# MCU.net
KiCad netlist of a schematic drawn in Altium Designer
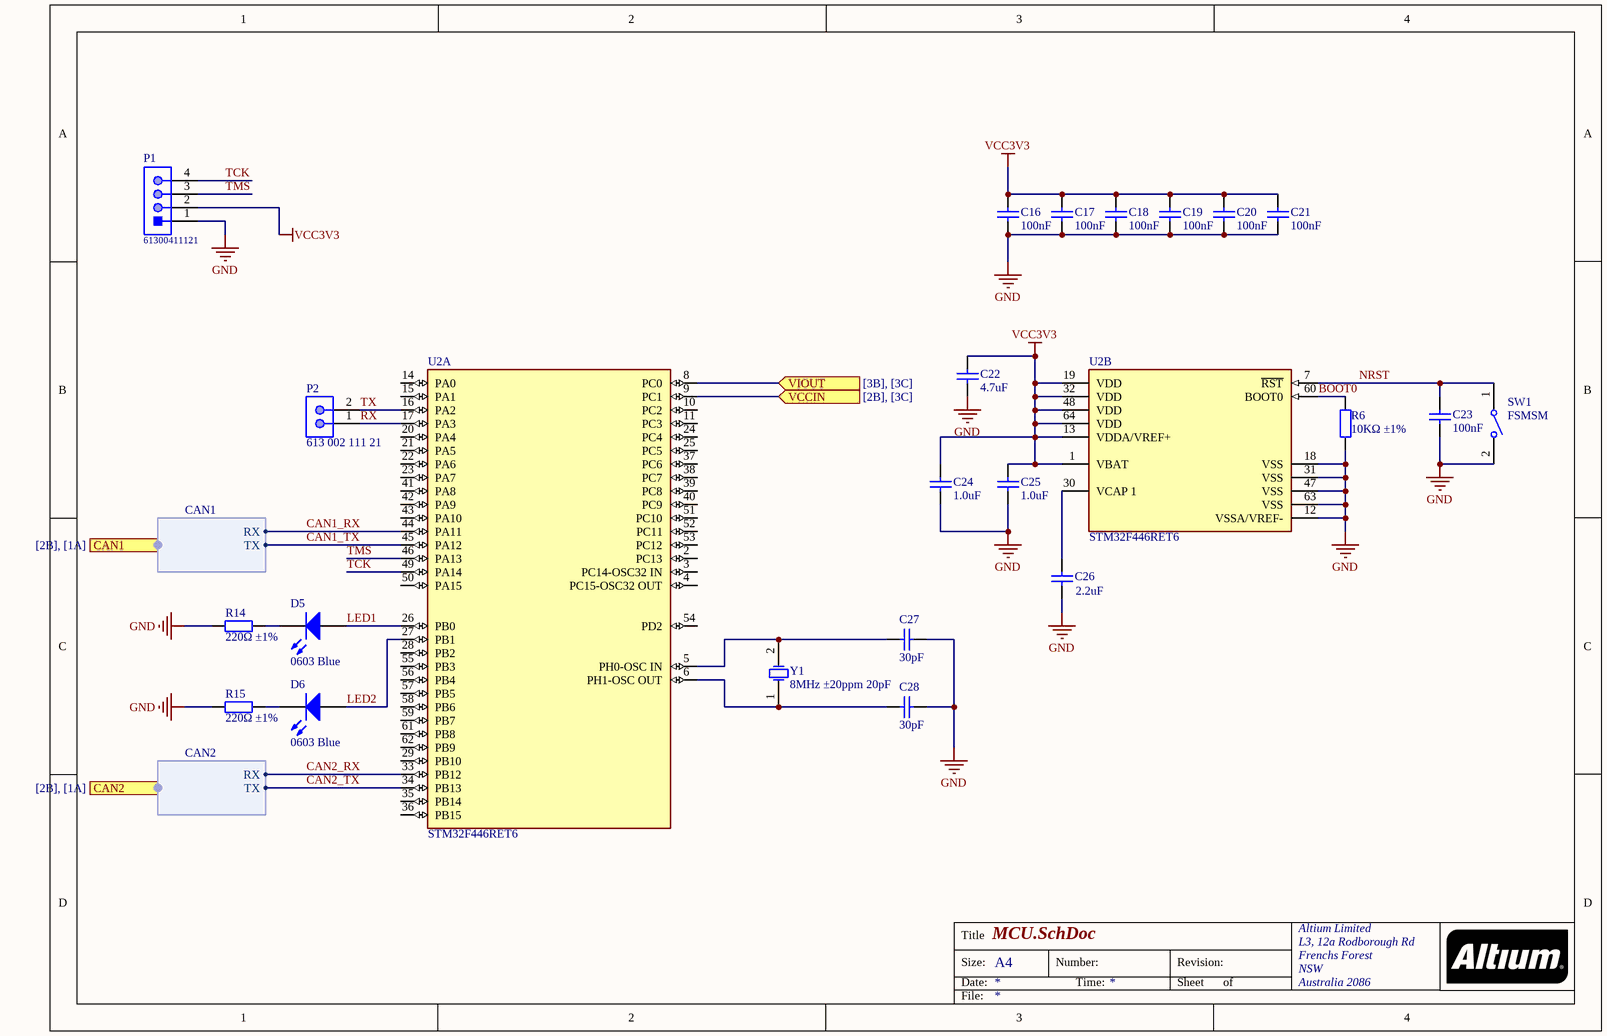
[diagram p0: MCU.SchDoc]

(export (version "E")
  (design (tool "Eeschema 10.0.6"))
  (components
    (comp (ref "C16")
      (value "100nF")
      (footprint "0402_C")
      (description "Chip capacitors")
      (fields
        (field (name "MANUFACTURER") "Samsung Electro-Mechanics")
        (field (name "PARTNUMBER") "CL05B104KO5NNNC")
      )
      (libsource (lib "Miscellaneous Devices LC") (part "0402 100nF (104) 10% 16V"))
    )
    (comp (ref "C17")
      (value "100nF")
      (footprint "0402_C")
      (description "Chip capacitors")
      (fields
        (field (name "MANUFACTURER") "Samsung Electro-Mechanics")
        (field (name "PARTNUMBER") "CL05B104KO5NNNC")
      )
      (libsource (lib "Miscellaneous Devices LC") (part "0402 100nF (104) 10% 16V"))
    )
    (comp (ref "C18")
      (value "100nF")
      (footprint "0402_C")
      (description "Chip capacitors")
      (fields
        (field (name "MANUFACTURER") "Samsung Electro-Mechanics")
        (field (name "PARTNUMBER") "CL05B104KO5NNNC")
      )
      (libsource (lib "Miscellaneous Devices LC") (part "0402 100nF (104) 10% 16V"))
    )
    (comp (ref "C19")
      (value "100nF")
      (footprint "0402_C")
      (description "Chip capacitors")
      (fields
        (field (name "MANUFACTURER") "Samsung Electro-Mechanics")
        (field (name "PARTNUMBER") "CL05B104KO5NNNC")
      )
      (libsource (lib "Miscellaneous Devices LC") (part "0402 100nF (104) 10% 16V"))
    )
    (comp (ref "C20")
      (value "100nF")
      (footprint "0402_C")
      (description "Chip capacitors")
      (fields
        (field (name "MANUFACTURER") "Samsung Electro-Mechanics")
        (field (name "PARTNUMBER") "CL05B104KO5NNNC")
      )
      (libsource (lib "Miscellaneous Devices LC") (part "0402 100nF (104) 10% 16V"))
    )
    (comp (ref "C21")
      (value "100nF")
      (footprint "0402_C")
      (description "Chip capacitors")
      (fields
        (field (name "MANUFACTURER") "Samsung Electro-Mechanics")
        (field (name "PARTNUMBER") "CL05B104KO5NNNC")
      )
      (libsource (lib "Miscellaneous Devices LC") (part "0402 100nF (104) 10% 16V"))
    )
    (comp (ref "C22")
      (value "4.7uF")
      (footprint "0402_C")
      (description "Chip capacitor")
      (fields
        (field (name "MANUFACTURER") "Samsung Electro-Mechanics")
        (field (name "PARTNUMBER") "CL05A475MP5NRNC")
      )
      (libsource (lib "Miscellaneous Devices LC") (part "0402 4.7uF (475) 20% 10V"))
    )
    (comp (ref "C23")
      (value "100nF")
      (footprint "0402_C")
      (description "Chip capacitors")
      (fields
        (field (name "MANUFACTURER") "Samsung Electro-Mechanics")
        (field (name "PARTNUMBER") "CL05B104KO5NNNC")
      )
      (libsource (lib "Miscellaneous Devices LC") (part "0402 100nF (104) 10% 16V"))
    )
    (comp (ref "C24")
      (value "1.0uF")
      (footprint "0402_C")
      (description "Chip capacitor")
      (fields
        (field (name "MANUFACTURER") "Samsung Electro-Mechanics")
        (field (name "PARTNUMBER") "CL05A105KA5NQNC")
      )
      (libsource (lib "Miscellaneous Devices LC") (part "0402 1.0uF (105) 10% 25V"))
    )
    (comp (ref "C25")
      (value "1.0uF")
      (footprint "0402_C")
      (description "Chip capacitor")
      (fields
        (field (name "MANUFACTURER") "Samsung Electro-Mechanics")
        (field (name "PARTNUMBER") "CL05A105KA5NQNC")
      )
      (libsource (lib "Miscellaneous Devices LC") (part "0402 1.0uF (105) 10% 25V"))
    )
    (comp (ref "C26")
      (value "2.2uF")
      (footprint "0603_C")
      (description "Chip capacitors")
      (fields
        (field (name "MANUFACTURER") "Samsung Electro-Mechanics")
        (field (name "PARTNUMBER") "CL10A225KO8NNNC")
      )
      (libsource (lib "Miscellaneous Devices LC") (part "0603 2.2uF (225) 10% 16V"))
    )
    (comp (ref "C27")
      (value "30pF")
      (footprint "0402_C")
      (description "Chip capacitors")
      (fields
        (field (name "MANUFACTURER") "Guangdong Fenghua Advanced Tech")
        (field (name "PARTNUMBER") "0402CG300J500NT")
      )
      (libsource (lib "Miscellaneous Devices LC") (part "0402 30pF (300) 5% 50V"))
    )
    (comp (ref "C28")
      (value "30pF")
      (footprint "0402_C")
      (description "Chip capacitors")
      (fields
        (field (name "MANUFACTURER") "Guangdong Fenghua Advanced Tech")
        (field (name "PARTNUMBER") "0402CG300J500NT")
      )
      (libsource (lib "Miscellaneous Devices LC") (part "0402 30pF (300) 5% 50V"))
    )
    (comp (ref "D5")
      (value "0603 Blue")
      (footprint "0603_LED_S1")
      (description "LED")
      (libsource (lib "Miscellaneous Devices LC") (part "0603 LED Blue"))
    )
    (comp (ref "D6")
      (value "0603 Blue")
      (footprint "0603_LED_S1")
      (description "LED")
      (libsource (lib "Miscellaneous Devices LC") (part "0603 LED Blue"))
    )
    (comp (ref "P1")
      (value "61300411121")
      (footprint "61300411121")
      (description "THT Vertical Pin Header WR-PHD, Pitch 2.54 mm, Single Row, 4 pins")
      (fields (field (name "MANUFACTURER") "Wurth Elektronik") (field (name "PUBLISHER") "WurthElektronik"))
      (libsource (lib "Altium Content Vault") (part "WE-CN-1P-M-R4"))
    )
    (comp (ref "P2")
      (value "613 002 111 21")
      (footprint "WE-61300211121_V")
      (libsource (lib "Altium Content Vault") (part "CN-1P-M-R2"))
    )
    (comp (ref "R6")
      (value "10KΩ ±1%")
      (footprint "0805_R")
      (description "Chip resistor")
      (fields (field (name "MANUFACTURER") "Uniroyal Elec") (field (name "POWER") "1/8W"))
      (libsource (lib "Miscellaneous Devices LC") (part "0805 10K (1002) 1%"))
    )
    (comp (ref "R14")
      (value "220Ω ±1%")
      (footprint "0402_R")
      (description "Chip resistor")
      (fields (field (name "MANUFACTURER") "Uniroyal Elec") (field (name "PARTNUMBER") "0402WGF2200TCE"))
      (libsource (lib "Miscellaneous Devices LC") (part "0402 220R (2200) 1%"))
    )
    (comp (ref "R15")
      (value "220Ω ±1%")
      (footprint "0402_R")
      (description "Chip resistor")
      (fields (field (name "MANUFACTURER") "Uniroyal Elec") (field (name "PARTNUMBER") "0402WGF2200TCE"))
      (libsource (lib "Miscellaneous Devices LC") (part "0402 220R (2200) 1%"))
    )
    (comp (ref "SW1")
      (value "FSMSM")
      (footprint "TECO-FSMSM-2_V")
      (description "FSMSM Push Button Switch, 50 mA, -35 to 85 degC, 2-Pin SMD, RoHS, Bulk")
      (fields (field (name "MANUFACTURER") "TE Connectivity"))
      (libsource (lib "Altium Content Vault") (part "SW-SPST-2_C"))
    )
    (comp (ref "U2")
      (value "STM32F446RET6")
      (footprint "FP-LQFP64-5W-MFG")
      (description "IC MCU 32BIT 512KB FLASH 64LQFP")
      (fields
        (field (name "OCTOPART") "https://octopart.com/stm32f446ret6-stmicroelectronics-52642920")
        (field (name "MANUFACTURER") "ST")
      )
      (libsource (lib "Altium Content Vault") (part "ee11adc32c0ab33b933cccf4348c338"))
    )
    (comp (ref "Y1")
      (value "8MHz ±20ppm 20pF")
      (footprint "SMD-5032_2P")
      (description "贴片晶振")
      (libsource (lib "Miscellaneous Devices LC") (part "SMD-5032_2P 8MHz 20ppm 20pF"))
    )
  )
  (nets
    (net (code "3") (name "/BOOT0") (class "Default")
      (node (ref "R6") (pin "2") (pinfunction "2_2") (pintype "passive"))
      (node (ref "U2") (pin "60") (pinfunction "BOOT0_60") (pintype "input"))
    )
    (net (code "4") (name "/CAN1_RX") (class "Default")
      (node (ref "U2") (pin "44") (pinfunction "PA11_44") (pintype "bidirectional"))
    )
    (net (code "5") (name "/CAN1_TX") (class "Default")
      (node (ref "U2") (pin "45") (pinfunction "PA12_45") (pintype "bidirectional"))
    )
    (net (code "6") (name "/CAN2_RX") (class "Default")
      (node (ref "U2") (pin "33") (pinfunction "PB12_33") (pintype "bidirectional"))
    )
    (net (code "7") (name "/CAN2_TX") (class "Default")
      (node (ref "U2") (pin "34") (pinfunction "PB13_34") (pintype "bidirectional"))
    )
    (net (code "8") (name "/LED1") (class "Default")
      (node (ref "D5") (pin "A") (pinfunction "A_A") (pintype "passive"))
      (node (ref "U2") (pin "26") (pinfunction "PB0_26") (pintype "bidirectional"))
    )
    (net (code "9") (name "/LED2") (class "Default")
      (node (ref "D6") (pin "A") (pinfunction "A_A") (pintype "passive"))
      (node (ref "U2") (pin "27") (pinfunction "PB1_27") (pintype "bidirectional"))
    )
    (net (code "10") (name "/NRST") (class "Default")
      (node (ref "C23") (pin "2") (pinfunction "2_2") (pintype "passive"))
      (node (ref "SW1") (pin "1") (pinfunction "1_1") (pintype "passive"))
      (node (ref "U2") (pin "7") (pinfunction "~{RST}_7") (pintype "input"))
    )
    (net (code "11") (name "/RX") (class "Default")
      (node (ref "P2") (pin "1") (pinfunction "1_1") (pintype "passive"))
      (node (ref "U2") (pin "17") (pinfunction "PA3_17") (pintype "bidirectional"))
    )
    (net (code "12") (name "/TCK") (class "Default")
      (node (ref "P1") (pin "4") (pinfunction "4_4") (pintype "passive"))
      (node (ref "U2") (pin "49") (pinfunction "PA14_49") (pintype "bidirectional"))
    )
    (net (code "13") (name "/TMS") (class "Default")
      (node (ref "P1") (pin "3") (pinfunction "3_3") (pintype "passive"))
      (node (ref "U2") (pin "46") (pinfunction "PA13_46") (pintype "bidirectional"))
    )
    (net (code "14") (name "/TX") (class "Default")
      (node (ref "P2") (pin "2") (pinfunction "2_2") (pintype "passive"))
      (node (ref "U2") (pin "16") (pinfunction "PA2_16") (pintype "bidirectional"))
    )
    (net (code "15") (name "/VCCIN") (class "Default")
      (node (ref "U2") (pin "9") (pinfunction "PC1_9") (pintype "bidirectional"))
    )
    (net (code "16") (name "/VIOUT") (class "Default")
      (node (ref "U2") (pin "8") (pinfunction "PC0_8") (pintype "bidirectional"))
    )
    (net (code "19") (name "GND") (class "Default")
      (node (ref "C16") (pin "1") (pinfunction "1_1") (pintype "passive"))
      (node (ref "C17") (pin "1") (pinfunction "1_1") (pintype "passive"))
      (node (ref "C18") (pin "1") (pinfunction "1_1") (pintype "passive"))
      (node (ref "C19") (pin "1") (pinfunction "1_1") (pintype "passive"))
      (node (ref "C20") (pin "1") (pinfunction "1_1") (pintype "passive"))
      (node (ref "C21") (pin "1") (pinfunction "1_1") (pintype "passive"))
      (node (ref "C22") (pin "1") (pinfunction "1_1") (pintype "passive"))
      (node (ref "C23") (pin "1") (pinfunction "1_1") (pintype "passive"))
      (node (ref "C24") (pin "1") (pinfunction "1_1") (pintype "passive"))
      (node (ref "C25") (pin "1") (pinfunction "1_1") (pintype "passive"))
      (node (ref "C26") (pin "1") (pinfunction "1_1") (pintype "passive"))
      (node (ref "C27") (pin "2") (pinfunction "2_2") (pintype "passive"))
      (node (ref "C28") (pin "2") (pinfunction "2_2") (pintype "passive"))
      (node (ref "P1") (pin "1") (pinfunction "1_1") (pintype "passive"))
      (node (ref "R14") (pin "1") (pinfunction "1_1") (pintype "passive"))
      (node (ref "R15") (pin "1") (pinfunction "1_1") (pintype "passive"))
      (node (ref "R6") (pin "1") (pinfunction "1_1") (pintype "passive"))
      (node (ref "SW1") (pin "2") (pinfunction "2_2") (pintype "passive"))
      (node (ref "U2") (pin "12") (pinfunction "VSSA/VREF-_12") (pintype "power_in"))
      (node (ref "U2") (pin "18") (pinfunction "VSS_18") (pintype "power_in"))
      (node (ref "U2") (pin "31") (pinfunction "VSS_31") (pintype "power_in"))
      (node (ref "U2") (pin "47") (pinfunction "VSS_47") (pintype "power_in"))
      (node (ref "U2") (pin "63") (pinfunction "VSS_63") (pintype "power_in"))
    )
    (net (code "20") (name "Net-(D5-PadK)") (class "Default")
      (node (ref "D5") (pin "K") (pinfunction "K_K") (pintype "passive"))
      (node (ref "R14") (pin "2") (pinfunction "2_2") (pintype "passive"))
    )
    (net (code "21") (name "Net-(D6-PadK)") (class "Default")
      (node (ref "D6") (pin "K") (pinfunction "K_K") (pintype "passive"))
      (node (ref "R15") (pin "2") (pinfunction "2_2") (pintype "passive"))
    )
    (net (code "22") (name "Net-(U2A-PH0-OSC_IN)") (class "Default")
      (node (ref "C27") (pin "1") (pinfunction "1_1") (pintype "passive"))
      (node (ref "U2") (pin "5") (pinfunction "PH0-OSC_IN_5") (pintype "bidirectional"))
      (node (ref "Y1") (pin "2") (pinfunction "OSC2_2") (pintype "passive"))
    )
    (net (code "23") (name "Net-(U2A-PH1-OSC_OUT)") (class "Default")
      (node (ref "C28") (pin "1") (pinfunction "1_1") (pintype "passive"))
      (node (ref "U2") (pin "6") (pinfunction "PH1-OSC_OUT_6") (pintype "bidirectional"))
      (node (ref "Y1") (pin "1") (pinfunction "OSC1_1") (pintype "passive"))
    )
    (net (code "24") (name "Net-(U2B-VCAP_1)") (class "Default")
      (node (ref "C26") (pin "2") (pinfunction "2_2") (pintype "passive"))
      (node (ref "U2") (pin "30") (pinfunction "VCAP_1_30") (pintype "power_in"))
    )
    (net (code "25") (name "VCC3V3") (class "Default")
      (node (ref "C16") (pin "2") (pinfunction "2_2") (pintype "passive"))
      (node (ref "C17") (pin "2") (pinfunction "2_2") (pintype "passive"))
      (node (ref "C18") (pin "2") (pinfunction "2_2") (pintype "passive"))
      (node (ref "C19") (pin "2") (pinfunction "2_2") (pintype "passive"))
      (node (ref "C20") (pin "2") (pinfunction "2_2") (pintype "passive"))
      (node (ref "C21") (pin "2") (pinfunction "2_2") (pintype "passive"))
      (node (ref "C22") (pin "2") (pinfunction "2_2") (pintype "passive"))
      (node (ref "C24") (pin "2") (pinfunction "2_2") (pintype "passive"))
      (node (ref "C25") (pin "2") (pinfunction "2_2") (pintype "passive"))
      (node (ref "P1") (pin "2") (pinfunction "2_2") (pintype "passive"))
      (node (ref "U2") (pin "1") (pinfunction "VBAT_1") (pintype "power_in"))
      (node (ref "U2") (pin "13") (pinfunction "VDDA/VREF+_13") (pintype "power_in"))
      (node (ref "U2") (pin "19") (pinfunction "VDD_19") (pintype "power_in"))
      (node (ref "U2") (pin "32") (pinfunction "VDD_32") (pintype "power_in"))
      (node (ref "U2") (pin "48") (pinfunction "VDD_48") (pintype "power_in"))
      (node (ref "U2") (pin "64") (pinfunction "VDD_64") (pintype "power_in"))
    )
    (net (code "26") (name "unconnected-(U2A-PA0-Pad14)") (class "Default")
      (node (ref "U2") (pin "14") (pinfunction "PA0_14") (pintype "bidirectional"))
    )
    (net (code "27") (name "unconnected-(U2A-PA1-Pad15)") (class "Default")
      (node (ref "U2") (pin "15") (pinfunction "PA1_15") (pintype "bidirectional"))
    )
    (net (code "28") (name "unconnected-(U2A-PA4-Pad20)") (class "Default")
      (node (ref "U2") (pin "20") (pinfunction "PA4_20") (pintype "bidirectional"))
    )
    (net (code "29") (name "unconnected-(U2A-PA5-Pad21)") (class "Default")
      (node (ref "U2") (pin "21") (pinfunction "PA5_21") (pintype "bidirectional"))
    )
    (net (code "30") (name "unconnected-(U2A-PA6-Pad22)") (class "Default")
      (node (ref "U2") (pin "22") (pinfunction "PA6_22") (pintype "bidirectional"))
    )
    (net (code "31") (name "unconnected-(U2A-PA7-Pad23)") (class "Default")
      (node (ref "U2") (pin "23") (pinfunction "PA7_23") (pintype "bidirectional"))
    )
    (net (code "32") (name "unconnected-(U2A-PA8-Pad41)") (class "Default")
      (node (ref "U2") (pin "41") (pinfunction "PA8_41") (pintype "bidirectional"))
    )
    (net (code "33") (name "unconnected-(U2A-PA9-Pad42)") (class "Default")
      (node (ref "U2") (pin "42") (pinfunction "PA9_42") (pintype "bidirectional"))
    )
    (net (code "34") (name "unconnected-(U2A-PA10-Pad43)") (class "Default")
      (node (ref "U2") (pin "43") (pinfunction "PA10_43") (pintype "bidirectional"))
    )
    (net (code "35") (name "unconnected-(U2A-PA15-Pad50)") (class "Default")
      (node (ref "U2") (pin "50") (pinfunction "PA15_50") (pintype "bidirectional"))
    )
    (net (code "36") (name "unconnected-(U2A-PB2-Pad28)") (class "Default")
      (node (ref "U2") (pin "28") (pinfunction "PB2_28") (pintype "bidirectional"))
    )
    (net (code "37") (name "unconnected-(U2A-PB3-Pad55)") (class "Default")
      (node (ref "U2") (pin "55") (pinfunction "PB3_55") (pintype "bidirectional"))
    )
    (net (code "38") (name "unconnected-(U2A-PB4-Pad56)") (class "Default")
      (node (ref "U2") (pin "56") (pinfunction "PB4_56") (pintype "bidirectional"))
    )
    (net (code "39") (name "unconnected-(U2A-PB5-Pad57)") (class "Default")
      (node (ref "U2") (pin "57") (pinfunction "PB5_57") (pintype "bidirectional"))
    )
    (net (code "40") (name "unconnected-(U2A-PB6-Pad58)") (class "Default")
      (node (ref "U2") (pin "58") (pinfunction "PB6_58") (pintype "bidirectional"))
    )
    (net (code "41") (name "unconnected-(U2A-PB7-Pad59)") (class "Default")
      (node (ref "U2") (pin "59") (pinfunction "PB7_59") (pintype "bidirectional"))
    )
    (net (code "42") (name "unconnected-(U2A-PB8-Pad61)") (class "Default")
      (node (ref "U2") (pin "61") (pinfunction "PB8_61") (pintype "bidirectional"))
    )
    (net (code "43") (name "unconnected-(U2A-PB9-Pad62)") (class "Default")
      (node (ref "U2") (pin "62") (pinfunction "PB9_62") (pintype "bidirectional"))
    )
    (net (code "44") (name "unconnected-(U2A-PB10-Pad29)") (class "Default")
      (node (ref "U2") (pin "29") (pinfunction "PB10_29") (pintype "bidirectional"))
    )
    (net (code "45") (name "unconnected-(U2A-PB14-Pad35)") (class "Default")
      (node (ref "U2") (pin "35") (pinfunction "PB14_35") (pintype "bidirectional"))
    )
    (net (code "46") (name "unconnected-(U2A-PB15-Pad36)") (class "Default")
      (node (ref "U2") (pin "36") (pinfunction "PB15_36") (pintype "bidirectional"))
    )
    (net (code "47") (name "unconnected-(U2A-PC2-Pad10)") (class "Default")
      (node (ref "U2") (pin "10") (pinfunction "PC2_10") (pintype "bidirectional"))
    )
    (net (code "48") (name "unconnected-(U2A-PC3-Pad11)") (class "Default")
      (node (ref "U2") (pin "11") (pinfunction "PC3_11") (pintype "bidirectional"))
    )
    (net (code "49") (name "unconnected-(U2A-PC4-Pad24)") (class "Default")
      (node (ref "U2") (pin "24") (pinfunction "PC4_24") (pintype "bidirectional"))
    )
    (net (code "50") (name "unconnected-(U2A-PC5-Pad25)") (class "Default")
      (node (ref "U2") (pin "25") (pinfunction "PC5_25") (pintype "bidirectional"))
    )
    (net (code "51") (name "unconnected-(U2A-PC6-Pad37)") (class "Default")
      (node (ref "U2") (pin "37") (pinfunction "PC6_37") (pintype "bidirectional"))
    )
    (net (code "52") (name "unconnected-(U2A-PC7-Pad38)") (class "Default")
      (node (ref "U2") (pin "38") (pinfunction "PC7_38") (pintype "bidirectional"))
    )
    (net (code "53") (name "unconnected-(U2A-PC8-Pad39)") (class "Default")
      (node (ref "U2") (pin "39") (pinfunction "PC8_39") (pintype "bidirectional"))
    )
    (net (code "54") (name "unconnected-(U2A-PC9-Pad40)") (class "Default")
      (node (ref "U2") (pin "40") (pinfunction "PC9_40") (pintype "bidirectional"))
    )
    (net (code "55") (name "unconnected-(U2A-PC10-Pad51)") (class "Default")
      (node (ref "U2") (pin "51") (pinfunction "PC10_51") (pintype "bidirectional"))
    )
    (net (code "56") (name "unconnected-(U2A-PC11-Pad52)") (class "Default")
      (node (ref "U2") (pin "52") (pinfunction "PC11_52") (pintype "bidirectional"))
    )
    (net (code "57") (name "unconnected-(U2A-PC12-Pad53)") (class "Default")
      (node (ref "U2") (pin "53") (pinfunction "PC12_53") (pintype "bidirectional"))
    )
    (net (code "58") (name "unconnected-(U2A-PC13-Pad2)") (class "Default")
      (node (ref "U2") (pin "2") (pinfunction "PC13_2") (pintype "bidirectional"))
    )
    (net (code "59") (name "unconnected-(U2A-PC14-OSC32_IN-Pad3)") (class "Default")
      (node (ref "U2") (pin "3") (pinfunction "PC14-OSC32_IN_3") (pintype "bidirectional"))
    )
    (net (code "60") (name "unconnected-(U2A-PC15-OSC32_OUT-Pad4)") (class "Default")
      (node (ref "U2") (pin "4") (pinfunction "PC15-OSC32_OUT_4") (pintype "bidirectional"))
    )
    (net (code "61") (name "unconnected-(U2A-PD2-Pad54)") (class "Default")
      (node (ref "U2") (pin "54") (pinfunction "PD2_54") (pintype "bidirectional"))
    )
  )
)
